# encoder_amplifier2.net
KiCad netlist of a schematic drawn in EAGLE
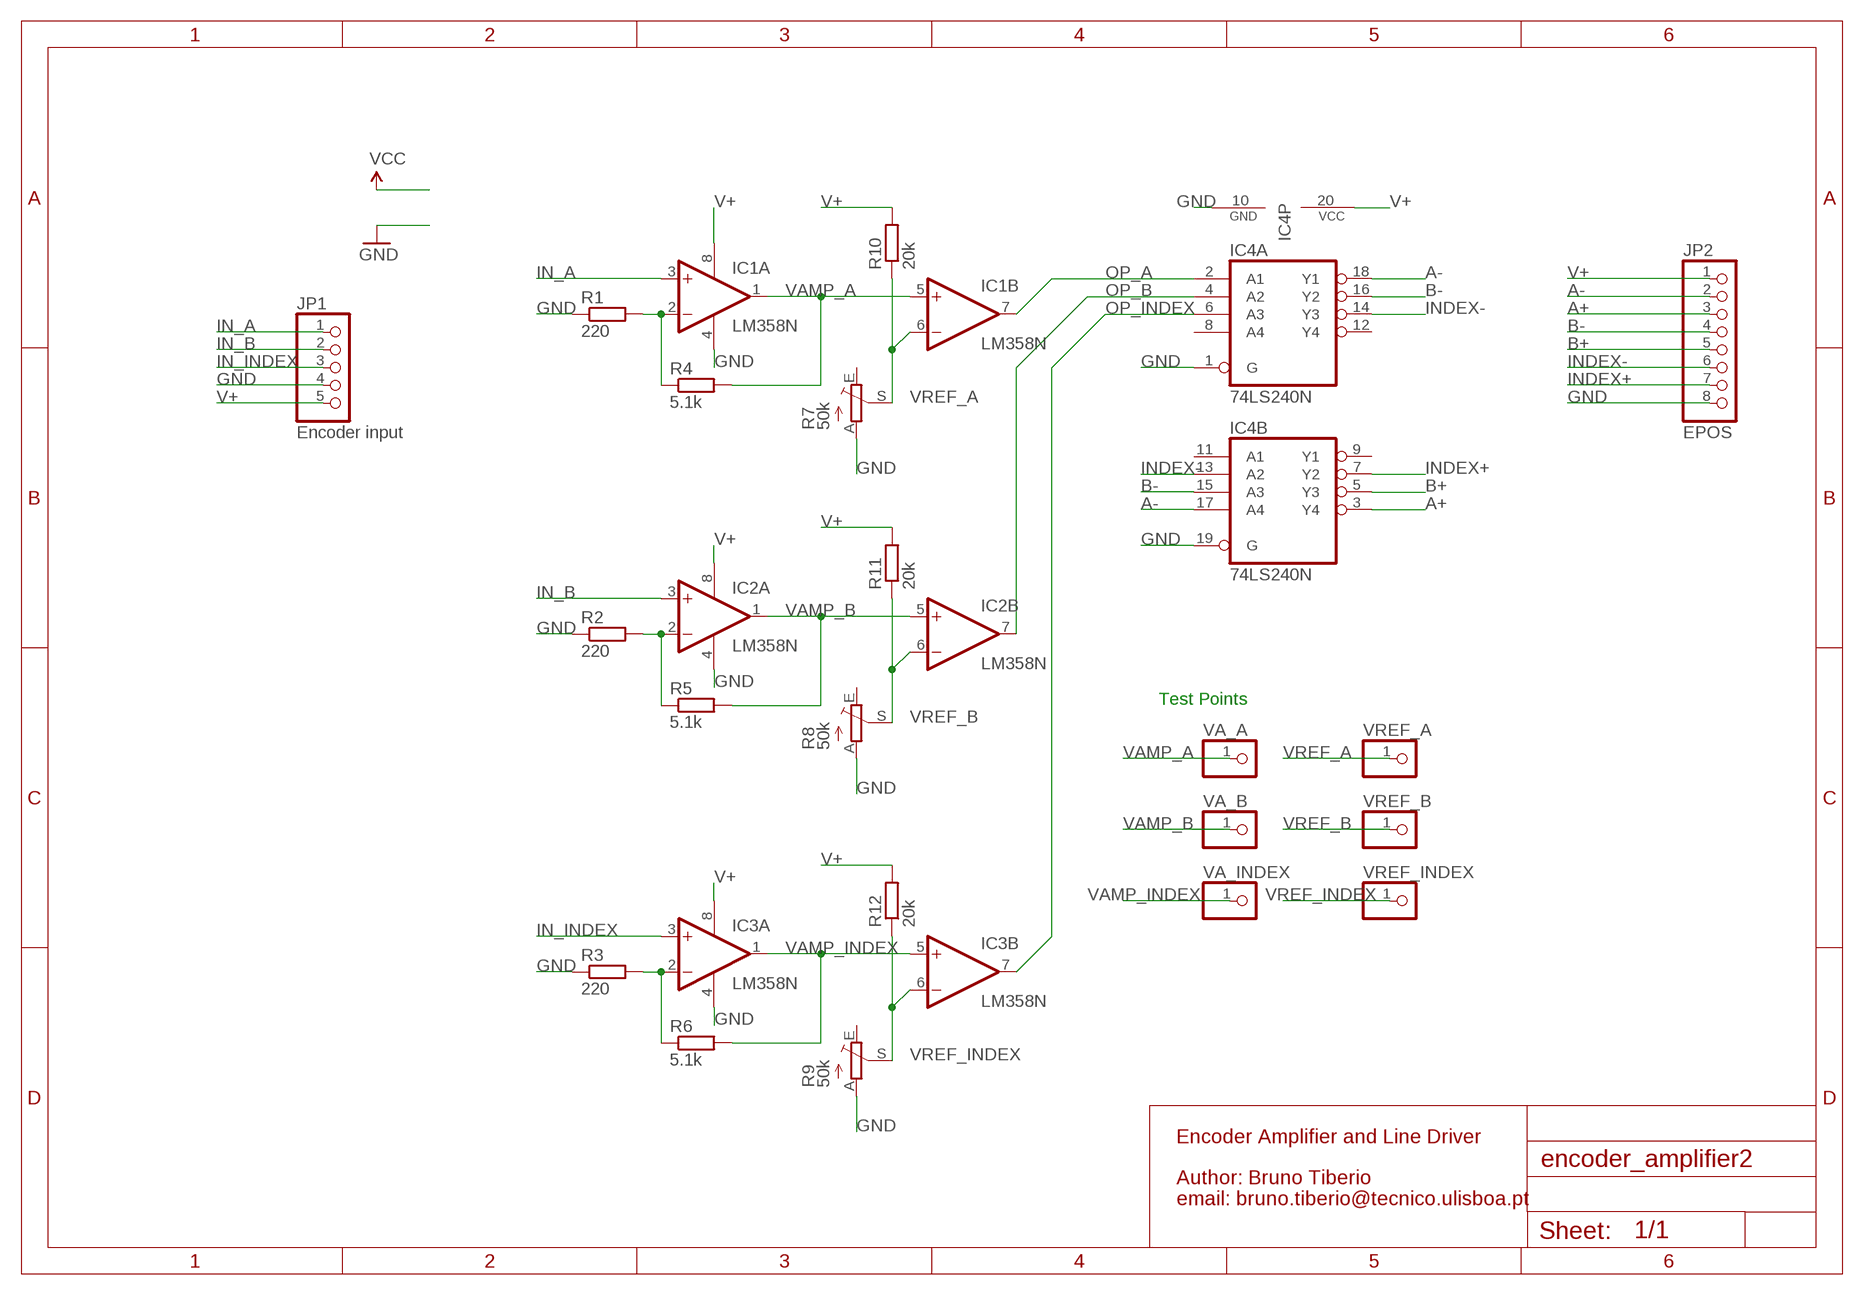
[diagram p0: schematic, sheet 1]

(export (version "E")
  (design (tool "Eeschema 10.0.6"))
  (components
    (comp (ref "IC1")
      (value "LM358N")
      (footprint "eagle-import:DIL08")
      (libsource (lib "eagle-import") (part "LM358N"))
    )
    (comp (ref "IC2")
      (value "LM358N")
      (footprint "eagle-import:DIL08")
      (libsource (lib "eagle-import") (part "LM358N"))
    )
    (comp (ref "IC3")
      (value "LM358N")
      (footprint "eagle-import:DIL08")
      (libsource (lib "eagle-import") (part "LM358N"))
    )
    (comp (ref "IC4")
      (value "74LS240N")
      (footprint "eagle-import:DIL20")
      (libsource (lib "eagle-import") (part "74240NLS"))
    )
    (comp (ref "JP1")
      (value "Encoder input")
      (footprint "eagle-import:1X05")
      (libsource (lib "eagle-import") (part "PINHD-1X5"))
    )
    (comp (ref "JP2")
      (value "EPOS")
      (footprint "eagle-import:1X08")
      (libsource (lib "eagle-import") (part "PINHD-1X8"))
    )
    (comp (ref "R1")
      (value "220")
      (footprint "eagle-import:0204_7")
      (libsource (lib "eagle-import") (part "R-EU_0204/7"))
    )
    (comp (ref "R2")
      (value "220")
      (footprint "eagle-import:0204_7")
      (libsource (lib "eagle-import") (part "R-EU_0204/7"))
    )
    (comp (ref "R3")
      (value "220")
      (footprint "eagle-import:0204_7")
      (libsource (lib "eagle-import") (part "R-EU_0204/7"))
    )
    (comp (ref "R4")
      (value "5.1k")
      (footprint "eagle-import:0204_7")
      (libsource (lib "eagle-import") (part "R-EU_0204/7"))
    )
    (comp (ref "R5")
      (value "5.1k")
      (footprint "eagle-import:0204_7")
      (libsource (lib "eagle-import") (part "R-EU_0204/7"))
    )
    (comp (ref "R6")
      (value "5.1k")
      (footprint "eagle-import:0204_7")
      (libsource (lib "eagle-import") (part "R-EU_0204/7"))
    )
    (comp (ref "R7")
      (value "50k")
      (footprint "eagle-import:LI15")
      (libsource (lib "eagle-import") (part "TRIM_EU-LI15"))
    )
    (comp (ref "R8")
      (value "50k")
      (footprint "eagle-import:LI15")
      (libsource (lib "eagle-import") (part "TRIM_EU-LI15"))
    )
    (comp (ref "R9")
      (value "50k")
      (footprint "eagle-import:LI15")
      (libsource (lib "eagle-import") (part "TRIM_EU-LI15"))
    )
    (comp (ref "R10")
      (value "20k")
      (footprint "eagle-import:0204_7")
      (libsource (lib "eagle-import") (part "R-EU_0204/7"))
    )
    (comp (ref "R11")
      (value "20k")
      (footprint "eagle-import:0204_7")
      (libsource (lib "eagle-import") (part "R-EU_0204/7"))
    )
    (comp (ref "R12")
      (value "20k")
      (footprint "eagle-import:0204_7")
      (libsource (lib "eagle-import") (part "R-EU_0204/7"))
    )
    (comp (ref "VA_A")
      (value "PINHD-1X1")
      (footprint "eagle-import:1X01")
      (libsource (lib "eagle-import") (part "PINHD-1X1"))
    )
    (comp (ref "VA_B")
      (value "PINHD-1X1")
      (footprint "eagle-import:1X01")
      (libsource (lib "eagle-import") (part "PINHD-1X1"))
    )
    (comp (ref "VA_INDEX")
      (value "PINHD-1X1")
      (footprint "eagle-import:1X01")
      (libsource (lib "eagle-import") (part "PINHD-1X1"))
    )
    (comp (ref "VREF_A")
      (value "PINHD-1X1")
      (footprint "eagle-import:1X01")
      (libsource (lib "eagle-import") (part "PINHD-1X1"))
    )
    (comp (ref "VREF_B")
      (value "PINHD-1X1")
      (footprint "eagle-import:1X01")
      (libsource (lib "eagle-import") (part "PINHD-1X1"))
    )
    (comp (ref "VREF_INDEX")
      (value "PINHD-1X1")
      (footprint "eagle-import:1X01")
      (libsource (lib "eagle-import") (part "PINHD-1X1"))
    )
  )
  (nets
    (net (code "1") (name "/A+") (class "Default")
      (node (ref "IC4") (pin "3") (pinfunction "Y4_3") (pintype "tri_state"))
      (node (ref "JP2") (pin "3") (pinfunction "3_3") (pintype "passive"))
    )
    (net (code "2") (name "/A-") (class "Default")
      (node (ref "IC4") (pin "17") (pinfunction "A4_17") (pintype "input"))
      (node (ref "IC4") (pin "18") (pinfunction "Y1_18") (pintype "tri_state"))
      (node (ref "JP2") (pin "2") (pinfunction "2_2") (pintype "passive"))
    )
    (net (code "3") (name "/B+") (class "Default")
      (node (ref "IC4") (pin "5") (pinfunction "Y3_5") (pintype "tri_state"))
      (node (ref "JP2") (pin "5") (pinfunction "5_5") (pintype "passive"))
    )
    (net (code "4") (name "/B-") (class "Default")
      (node (ref "IC4") (pin "15") (pinfunction "A3_15") (pintype "input"))
      (node (ref "IC4") (pin "16") (pinfunction "Y2_16") (pintype "tri_state"))
      (node (ref "JP2") (pin "4") (pinfunction "4_4") (pintype "passive"))
    )
    (net (code "5") (name "/INDEX+") (class "Default")
      (node (ref "IC4") (pin "7") (pinfunction "Y2_7") (pintype "tri_state"))
      (node (ref "JP2") (pin "7") (pinfunction "7_7") (pintype "passive"))
    )
    (net (code "6") (name "/INDEX-") (class "Default")
      (node (ref "IC4") (pin "13") (pinfunction "A2_13") (pintype "input"))
      (node (ref "IC4") (pin "14") (pinfunction "Y3_14") (pintype "tri_state"))
      (node (ref "JP2") (pin "6") (pinfunction "6_6") (pintype "passive"))
    )
    (net (code "7") (name "/IN_A") (class "Default")
      (node (ref "IC1") (pin "3") (pinfunction "+IN_3") (pintype "input"))
      (node (ref "JP1") (pin "1") (pinfunction "1_1") (pintype "passive"))
    )
    (net (code "8") (name "/IN_B") (class "Default")
      (node (ref "IC2") (pin "3") (pinfunction "+IN_3") (pintype "input"))
      (node (ref "JP1") (pin "2") (pinfunction "2_2") (pintype "passive"))
    )
    (net (code "9") (name "/IN_INDEX") (class "Default")
      (node (ref "IC3") (pin "3") (pinfunction "+IN_3") (pintype "input"))
      (node (ref "JP1") (pin "3") (pinfunction "3_3") (pintype "passive"))
    )
    (net (code "10") (name "/OP_A") (class "Default")
      (node (ref "IC1") (pin "7") (pinfunction "OUT_7") (pintype "output"))
      (node (ref "IC4") (pin "2") (pinfunction "A1_2") (pintype "input"))
    )
    (net (code "11") (name "/OP_B") (class "Default")
      (node (ref "IC2") (pin "7") (pinfunction "OUT_7") (pintype "output"))
      (node (ref "IC4") (pin "4") (pinfunction "A2_4") (pintype "input"))
    )
    (net (code "12") (name "/OP_INDEX") (class "Default")
      (node (ref "IC3") (pin "7") (pinfunction "OUT_7") (pintype "output"))
      (node (ref "IC4") (pin "6") (pinfunction "A3_6") (pintype "input"))
    )
    (net (code "13") (name "/V+") (class "Default")
      (node (ref "IC1") (pin "8") (pinfunction "V+_8") (pintype "power_in"))
      (node (ref "IC2") (pin "8") (pinfunction "V+_8") (pintype "power_in"))
      (node (ref "IC3") (pin "8") (pinfunction "V+_8") (pintype "power_in"))
      (node (ref "IC4") (pin "20") (pinfunction "VCC_20") (pintype "power_in"))
      (node (ref "JP1") (pin "5") (pinfunction "5_5") (pintype "passive"))
      (node (ref "JP2") (pin "1") (pinfunction "1_1") (pintype "passive"))
      (node (ref "R10") (pin "2") (pinfunction "2_2") (pintype "passive"))
      (node (ref "R11") (pin "2") (pinfunction "2_2") (pintype "passive"))
      (node (ref "R12") (pin "2") (pinfunction "2_2") (pintype "passive"))
    )
    (net (code "14") (name "/VAMP_A") (class "Default")
      (node (ref "IC1") (pin "1") (pinfunction "OUT_1") (pintype "output"))
      (node (ref "IC1") (pin "5") (pinfunction "+IN_5") (pintype "input"))
      (node (ref "R4") (pin "2") (pinfunction "2_2") (pintype "passive"))
      (node (ref "VA_A") (pin "1") (pinfunction "1_1") (pintype "passive"))
    )
    (net (code "15") (name "/VAMP_B") (class "Default")
      (node (ref "IC2") (pin "1") (pinfunction "OUT_1") (pintype "output"))
      (node (ref "IC2") (pin "5") (pinfunction "+IN_5") (pintype "input"))
      (node (ref "R5") (pin "2") (pinfunction "2_2") (pintype "passive"))
      (node (ref "VA_B") (pin "1") (pinfunction "1_1") (pintype "passive"))
    )
    (net (code "16") (name "/VAMP_INDEX") (class "Default")
      (node (ref "IC3") (pin "1") (pinfunction "OUT_1") (pintype "output"))
      (node (ref "IC3") (pin "5") (pinfunction "+IN_5") (pintype "input"))
      (node (ref "R6") (pin "2") (pinfunction "2_2") (pintype "passive"))
      (node (ref "VA_INDEX") (pin "1") (pinfunction "1_1") (pintype "passive"))
    )
    (net (code "17") (name "/VREF_A") (class "Default")
      (node (ref "IC1") (pin "6") (pinfunction "-IN_6") (pintype "input"))
      (node (ref "R10") (pin "1") (pinfunction "1_1") (pintype "passive"))
      (node (ref "R7") (pin "S") (pinfunction "S_S") (pintype "passive"))
      (node (ref "VREF_A") (pin "1") (pinfunction "1_1") (pintype "passive"))
    )
    (net (code "18") (name "/VREF_B") (class "Default")
      (node (ref "IC2") (pin "6") (pinfunction "-IN_6") (pintype "input"))
      (node (ref "R11") (pin "1") (pinfunction "1_1") (pintype "passive"))
      (node (ref "R8") (pin "S") (pinfunction "S_S") (pintype "passive"))
      (node (ref "VREF_B") (pin "1") (pinfunction "1_1") (pintype "passive"))
    )
    (net (code "19") (name "/VREF_INDEX") (class "Default")
      (node (ref "IC3") (pin "6") (pinfunction "-IN_6") (pintype "input"))
      (node (ref "R12") (pin "1") (pinfunction "1_1") (pintype "passive"))
      (node (ref "R9") (pin "S") (pinfunction "S_S") (pintype "passive"))
      (node (ref "VREF_INDEX") (pin "1") (pinfunction "1_1") (pintype "passive"))
    )
    (net (code "20") (name "GND") (class "Default")
      (node (ref "IC1") (pin "4") (pinfunction "V-_4") (pintype "power_in"))
      (node (ref "IC2") (pin "4") (pinfunction "V-_4") (pintype "power_in"))
      (node (ref "IC3") (pin "4") (pinfunction "V-_4") (pintype "power_in"))
      (node (ref "IC4") (pin "1") (pinfunction "G_1") (pintype "input"))
      (node (ref "IC4") (pin "10") (pinfunction "GND_10") (pintype "power_in"))
      (node (ref "IC4") (pin "19") (pinfunction "G_19") (pintype "input"))
      (node (ref "JP1") (pin "4") (pinfunction "4_4") (pintype "passive"))
      (node (ref "JP2") (pin "8") (pinfunction "8_8") (pintype "passive"))
      (node (ref "R1") (pin "1") (pinfunction "1_1") (pintype "passive"))
      (node (ref "R2") (pin "1") (pinfunction "1_1") (pintype "passive"))
      (node (ref "R3") (pin "1") (pinfunction "1_1") (pintype "passive"))
      (node (ref "R7") (pin "A") (pinfunction "A_A") (pintype "passive"))
      (node (ref "R8") (pin "A") (pinfunction "A_A") (pintype "passive"))
      (node (ref "R9") (pin "A") (pinfunction "A_A") (pintype "passive"))
    )
    (net (code "21") (name "Net-(IC1A--IN)") (class "Default")
      (node (ref "IC1") (pin "2") (pinfunction "-IN_2") (pintype "input"))
      (node (ref "R1") (pin "2") (pinfunction "2_2") (pintype "passive"))
      (node (ref "R4") (pin "1") (pinfunction "1_1") (pintype "passive"))
    )
    (net (code "22") (name "Net-(IC2A--IN)") (class "Default")
      (node (ref "IC2") (pin "2") (pinfunction "-IN_2") (pintype "input"))
      (node (ref "R2") (pin "2") (pinfunction "2_2") (pintype "passive"))
      (node (ref "R5") (pin "1") (pinfunction "1_1") (pintype "passive"))
    )
    (net (code "23") (name "Net-(IC3A--IN)") (class "Default")
      (node (ref "IC3") (pin "2") (pinfunction "-IN_2") (pintype "input"))
      (node (ref "R3") (pin "2") (pinfunction "2_2") (pintype "passive"))
      (node (ref "R6") (pin "1") (pinfunction "1_1") (pintype "passive"))
    )
    (net (code "25") (name "unconnected-(IC4A-A4-Pad8)") (class "Default")
      (node (ref "IC4") (pin "8") (pinfunction "A4_8") (pintype "input"))
    )
    (net (code "26") (name "unconnected-(IC4A-Y4-Pad12)") (class "Default")
      (node (ref "IC4") (pin "12") (pinfunction "Y4_12") (pintype "tri_state"))
    )
    (net (code "27") (name "unconnected-(IC4B-A1-Pad11)") (class "Default")
      (node (ref "IC4") (pin "11") (pinfunction "A1_11") (pintype "input"))
    )
    (net (code "28") (name "unconnected-(IC4B-Y1-Pad9)") (class "Default")
      (node (ref "IC4") (pin "9") (pinfunction "Y1_9") (pintype "tri_state"))
    )
    (net (code "29") (name "unconnected-(R7-PadE)") (class "Default")
      (node (ref "R7") (pin "E") (pinfunction "E_E") (pintype "passive"))
    )
    (net (code "30") (name "unconnected-(R8-PadE)") (class "Default")
      (node (ref "R8") (pin "E") (pinfunction "E_E") (pintype "passive"))
    )
    (net (code "31") (name "unconnected-(R9-PadE)") (class "Default")
      (node (ref "R9") (pin "E") (pinfunction "E_E") (pintype "passive"))
    )
  )
)
